# STMv1.net
KiCad netlist of a schematic drawn in EAGLE
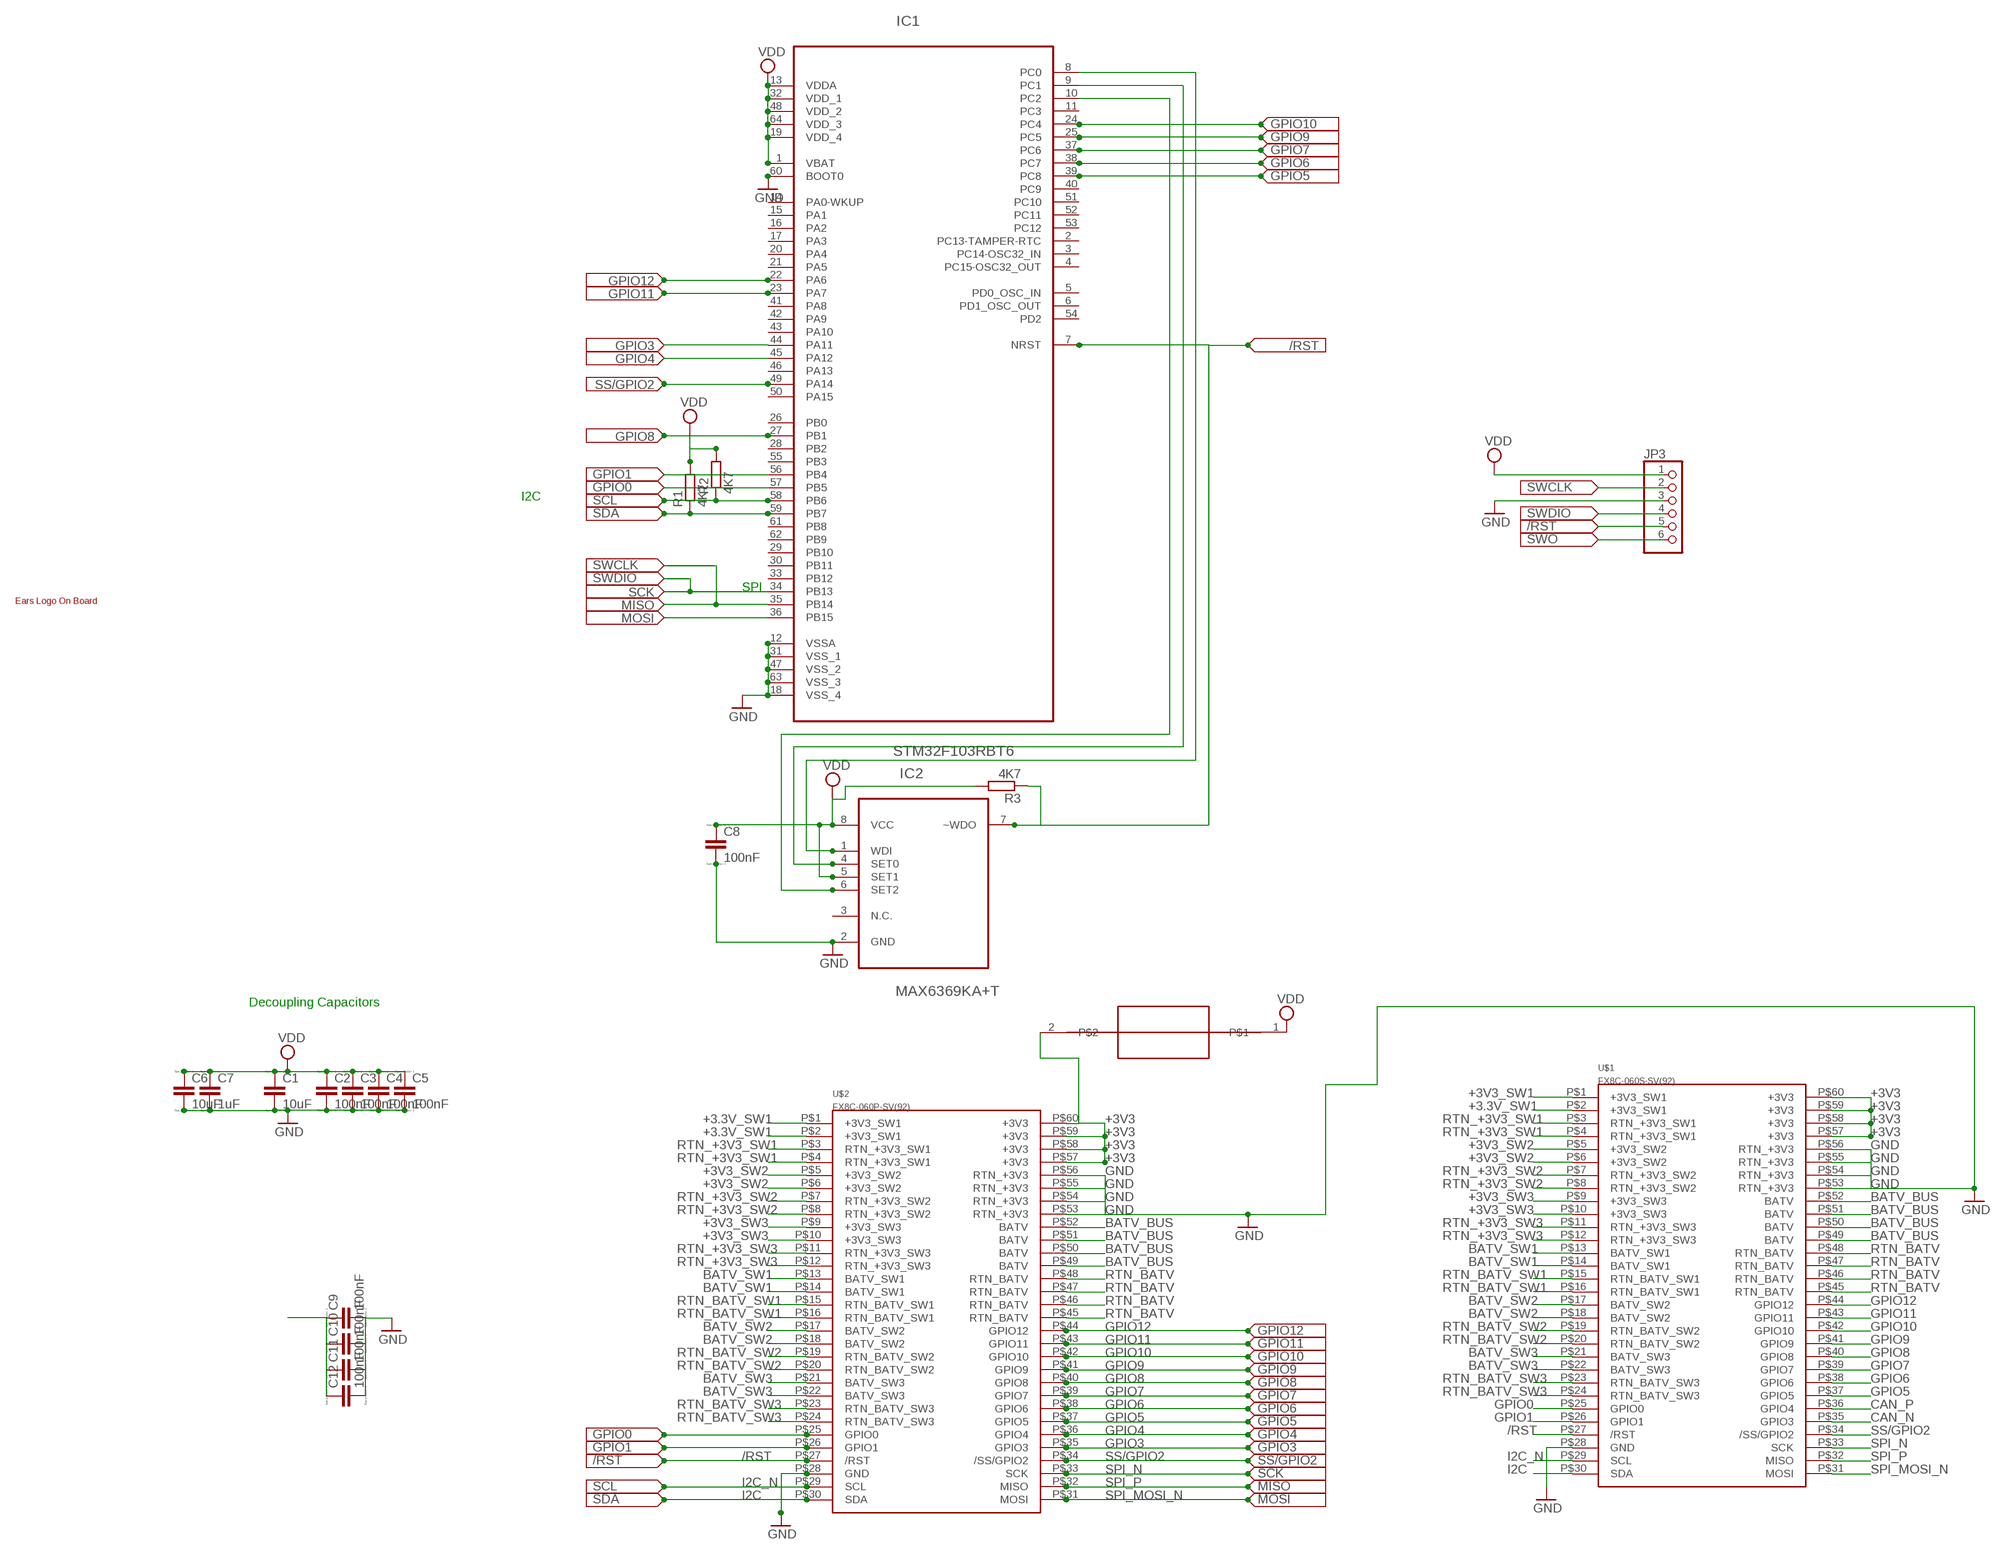
[diagram p0: schematic, sheet 1]

(export (version "E")
  (design (tool "Eeschema 10.0.6"))
  (components
    (comp (ref "C1")
      (value "10uF")
      (footprint "eagle-import:C0603")
      (libsource (lib "eagle-import") (part "CC0603"))
    )
    (comp (ref "C2")
      (value "100nF")
      (footprint "eagle-import:C0603")
      (libsource (lib "eagle-import") (part "CC0603"))
    )
    (comp (ref "C3")
      (value "100nF")
      (footprint "eagle-import:C0603")
      (libsource (lib "eagle-import") (part "CC0603"))
    )
    (comp (ref "C4")
      (value "100nF")
      (footprint "eagle-import:C0603")
      (libsource (lib "eagle-import") (part "CC0603"))
    )
    (comp (ref "C5")
      (value "100nF")
      (footprint "eagle-import:C0603")
      (libsource (lib "eagle-import") (part "CC0603"))
    )
    (comp (ref "C6")
      (value "10uF")
      (footprint "eagle-import:C0603")
      (libsource (lib "eagle-import") (part "CC0603"))
    )
    (comp (ref "C7")
      (value "1uF")
      (footprint "eagle-import:C0603")
      (libsource (lib "eagle-import") (part "CC0603"))
    )
    (comp (ref "C8")
      (value "100nF")
      (footprint "eagle-import:C0603")
      (libsource (lib "eagle-import") (part "CC0603"))
    )
    (comp (ref "C9")
      (value "100nF")
      (footprint "eagle-import:C0603")
      (libsource (lib "eagle-import") (part "CC0603"))
    )
    (comp (ref "C10")
      (value "100nF")
      (footprint "eagle-import:C0603")
      (libsource (lib "eagle-import") (part "CC0603"))
    )
    (comp (ref "C11")
      (value "100nF")
      (footprint "eagle-import:C0603")
      (libsource (lib "eagle-import") (part "CC0603"))
    )
    (comp (ref "C12")
      (value "100nF")
      (footprint "eagle-import:C0603")
      (libsource (lib "eagle-import") (part "CC0603"))
    )
    (comp (ref "FUSE")
      (value "0603POLYFUSE")
      (footprint "eagle-import:R0603")
      (libsource (lib "eagle-import") (part "0603POLYFUSE"))
    )
    (comp (ref "IC1")
      (value "STM32F103RBT6")
      (footprint "eagle-import:QFP50P1200X1200X160-64N")
      (libsource (lib "eagle-import") (part "STM32F103RBT6"))
    )
    (comp (ref "IC2")
      (value "MAX6369KA+T")
      (footprint "eagle-import:SOT65P280X145-8N")
      (libsource (lib "eagle-import") (part "MAX6369KA+T"))
    )
    (comp (ref "JP3")
      (value "PINHD-1X6")
      (footprint "eagle-import:1X06")
      (libsource (lib "eagle-import") (part "PINHD-1X6"))
    )
    (comp (ref "R1")
      (value "4K7")
      (footprint "eagle-import:R0603")
      (libsource (lib "eagle-import") (part "R-EU_R0603"))
    )
    (comp (ref "R2")
      (value "4K7")
      (footprint "eagle-import:R0603")
      (libsource (lib "eagle-import") (part "R-EU_R0603"))
    )
    (comp (ref "R3")
      (value "4K7")
      (footprint "eagle-import:R0603")
      (libsource (lib "eagle-import") (part "R-EU_R0603"))
    )
    (comp (ref "U$1")
      (value "FX8C-060S-SV(92)")
      (footprint "eagle-import:FX8C-060S-SV(92)")
      (libsource (lib "eagle-import") (part "FX8C-060S-SV(92)"))
    )
    (comp (ref "U$2")
      (value "FX8C-060P-SV(92)")
      (footprint "eagle-import:FX8C-060P-SV(92)")
      (libsource (lib "eagle-import") (part "FX8C-060P-SV(92)"))
    )
    (comp (ref "U$3")
      (value "EARSLOGOFULL")
      (footprint "eagle-import:EARSLOGOFULL")
      (libsource (lib "eagle-import") (part "EARSLOGOFULL"))
    )
  )
  (nets
    (net (code "1") (name "/+3.3V_SW1") (class "Default")
      (node (ref "U$1") (pin "P$2") (pinfunction "+3V3_SW1_P$2") (pintype "power_in"))
      (node (ref "U$2") (pin "P$1") (pinfunction "+3V3_SW1_P$1") (pintype "power_in"))
      (node (ref "U$2") (pin "P$2") (pinfunction "+3V3_SW1_P$2") (pintype "power_in"))
    )
    (net (code "2") (name "/+3V3") (class "Default")
      (node (ref "FUSE") (pin "2") (pinfunction "P$2_2") (pintype "bidirectional"))
      (node (ref "U$1") (pin "P$57") (pinfunction "+3V3_P$57") (pintype "power_in"))
      (node (ref "U$1") (pin "P$58") (pinfunction "+3V3_P$58") (pintype "power_in"))
      (node (ref "U$1") (pin "P$59") (pinfunction "+3V3_P$59") (pintype "power_in"))
      (node (ref "U$1") (pin "P$60") (pinfunction "+3V3_P$60") (pintype "power_in"))
      (node (ref "U$2") (pin "P$57") (pinfunction "+3V3_P$57") (pintype "power_in"))
      (node (ref "U$2") (pin "P$58") (pinfunction "+3V3_P$58") (pintype "power_in"))
      (node (ref "U$2") (pin "P$59") (pinfunction "+3V3_P$59") (pintype "power_in"))
      (node (ref "U$2") (pin "P$60") (pinfunction "+3V3_P$60") (pintype "power_in"))
    )
    (net (code "3") (name "/+3V3_SW1") (class "Default")
      (node (ref "U$1") (pin "P$1") (pinfunction "+3V3_SW1_P$1") (pintype "power_in"))
    )
    (net (code "4") (name "/+3V3_SW2") (class "Default")
      (node (ref "U$1") (pin "P$5") (pinfunction "+3V3_SW2_P$5") (pintype "power_in"))
      (node (ref "U$1") (pin "P$6") (pinfunction "+3V3_SW2_P$6") (pintype "power_in"))
      (node (ref "U$2") (pin "P$5") (pinfunction "+3V3_SW2_P$5") (pintype "power_in"))
      (node (ref "U$2") (pin "P$6") (pinfunction "+3V3_SW2_P$6") (pintype "power_in"))
    )
    (net (code "5") (name "/+3V3_SW3") (class "Default")
      (node (ref "U$1") (pin "P$10") (pinfunction "+3V3_SW3_P$10") (pintype "power_in"))
      (node (ref "U$1") (pin "P$9") (pinfunction "+3V3_SW3_P$9") (pintype "power_in"))
      (node (ref "U$2") (pin "P$10") (pinfunction "+3V3_SW3_P$10") (pintype "power_in"))
      (node (ref "U$2") (pin "P$9") (pinfunction "+3V3_SW3_P$9") (pintype "power_in"))
    )
    (net (code "6") (name "/BATV_BUS") (class "Default")
      (node (ref "U$1") (pin "P$49") (pinfunction "BATV_P$49") (pintype "power_in"))
      (node (ref "U$1") (pin "P$50") (pinfunction "BATV_P$50") (pintype "power_in"))
      (node (ref "U$1") (pin "P$51") (pinfunction "BATV_P$51") (pintype "power_in"))
      (node (ref "U$1") (pin "P$52") (pinfunction "BATV_P$52") (pintype "power_in"))
      (node (ref "U$2") (pin "P$49") (pinfunction "BATV_P$49") (pintype "power_in"))
      (node (ref "U$2") (pin "P$50") (pinfunction "BATV_P$50") (pintype "power_in"))
      (node (ref "U$2") (pin "P$51") (pinfunction "BATV_P$51") (pintype "power_in"))
      (node (ref "U$2") (pin "P$52") (pinfunction "BATV_P$52") (pintype "power_in"))
    )
    (net (code "7") (name "/BATV_SW1") (class "Default")
      (node (ref "U$1") (pin "P$13") (pinfunction "BATV_SW1_P$13") (pintype "power_in"))
      (node (ref "U$1") (pin "P$14") (pinfunction "BATV_SW1_P$14") (pintype "power_in"))
      (node (ref "U$2") (pin "P$13") (pinfunction "BATV_SW1_P$13") (pintype "power_in"))
      (node (ref "U$2") (pin "P$14") (pinfunction "BATV_SW1_P$14") (pintype "power_in"))
    )
    (net (code "8") (name "/BATV_SW2") (class "Default")
      (node (ref "U$1") (pin "P$17") (pinfunction "BATV_SW2_P$17") (pintype "power_in"))
      (node (ref "U$1") (pin "P$18") (pinfunction "BATV_SW2_P$18") (pintype "power_in"))
      (node (ref "U$2") (pin "P$17") (pinfunction "BATV_SW2_P$17") (pintype "power_in"))
      (node (ref "U$2") (pin "P$18") (pinfunction "BATV_SW2_P$18") (pintype "power_in"))
    )
    (net (code "9") (name "/BATV_SW3") (class "Default")
      (node (ref "U$1") (pin "P$21") (pinfunction "BATV_SW3_P$21") (pintype "power_in"))
      (node (ref "U$1") (pin "P$22") (pinfunction "BATV_SW3_P$22") (pintype "power_in"))
      (node (ref "U$2") (pin "P$21") (pinfunction "BATV_SW3_P$21") (pintype "power_in"))
      (node (ref "U$2") (pin "P$22") (pinfunction "BATV_SW3_P$22") (pintype "power_in"))
    )
    (net (code "10") (name "/CAN_N") (class "Default")
      (node (ref "U$1") (pin "P$35") (pinfunction "GPIO3_P$35") (pintype "bidirectional"))
    )
    (net (code "11") (name "/CAN_P") (class "Default")
      (node (ref "U$1") (pin "P$36") (pinfunction "GPIO4_P$36") (pintype "bidirectional"))
    )
    (net (code "12") (name "/GPIO0") (class "Default")
      (node (ref "IC1") (pin "57") (pinfunction "PB5_57") (pintype "bidirectional"))
      (node (ref "U$1") (pin "P$25") (pinfunction "GPIO0_P$25") (pintype "bidirectional"))
      (node (ref "U$2") (pin "P$25") (pinfunction "GPIO0_P$25") (pintype "bidirectional"))
    )
    (net (code "13") (name "/GPIO1") (class "Default")
      (node (ref "IC1") (pin "56") (pinfunction "PB4_56") (pintype "bidirectional"))
      (node (ref "U$1") (pin "P$26") (pinfunction "GPIO1_P$26") (pintype "bidirectional"))
      (node (ref "U$2") (pin "P$26") (pinfunction "GPIO1_P$26") (pintype "bidirectional"))
    )
    (net (code "14") (name "/GPIO3") (class "Default")
      (node (ref "IC1") (pin "44") (pinfunction "PA11_44") (pintype "bidirectional"))
      (node (ref "U$2") (pin "P$35") (pinfunction "GPIO3_P$35") (pintype "bidirectional"))
    )
    (net (code "15") (name "/GPIO4") (class "Default")
      (node (ref "IC1") (pin "45") (pinfunction "PA12_45") (pintype "bidirectional"))
      (node (ref "U$2") (pin "P$36") (pinfunction "GPIO4_P$36") (pintype "bidirectional"))
    )
    (net (code "16") (name "/GPIO5") (class "Default")
      (node (ref "IC1") (pin "39") (pinfunction "PC8_39") (pintype "bidirectional"))
      (node (ref "U$1") (pin "P$37") (pinfunction "GPIO5_P$37") (pintype "bidirectional"))
      (node (ref "U$2") (pin "P$37") (pinfunction "GPIO5_P$37") (pintype "bidirectional"))
    )
    (net (code "17") (name "/GPIO6") (class "Default")
      (node (ref "IC1") (pin "38") (pinfunction "PC7_38") (pintype "bidirectional"))
      (node (ref "U$1") (pin "P$38") (pinfunction "GPIO6_P$38") (pintype "bidirectional"))
      (node (ref "U$2") (pin "P$38") (pinfunction "GPIO6_P$38") (pintype "bidirectional"))
    )
    (net (code "18") (name "/GPIO7") (class "Default")
      (node (ref "IC1") (pin "37") (pinfunction "PC6_37") (pintype "bidirectional"))
      (node (ref "U$1") (pin "P$39") (pinfunction "GPIO7_P$39") (pintype "bidirectional"))
      (node (ref "U$2") (pin "P$39") (pinfunction "GPIO7_P$39") (pintype "bidirectional"))
    )
    (net (code "19") (name "/GPIO8") (class "Default")
      (node (ref "IC1") (pin "27") (pinfunction "PB1_27") (pintype "bidirectional"))
      (node (ref "U$1") (pin "P$40") (pinfunction "GPIO8_P$40") (pintype "bidirectional"))
      (node (ref "U$2") (pin "P$40") (pinfunction "GPIO8_P$40") (pintype "bidirectional"))
    )
    (net (code "20") (name "/GPIO9") (class "Default")
      (node (ref "IC1") (pin "25") (pinfunction "PC5_25") (pintype "bidirectional"))
      (node (ref "U$1") (pin "P$41") (pinfunction "GPIO9_P$41") (pintype "bidirectional"))
      (node (ref "U$2") (pin "P$41") (pinfunction "GPIO9_P$41") (pintype "bidirectional"))
    )
    (net (code "21") (name "/GPIO10") (class "Default")
      (node (ref "IC1") (pin "24") (pinfunction "PC4_24") (pintype "bidirectional"))
      (node (ref "U$1") (pin "P$42") (pinfunction "GPIO10_P$42") (pintype "bidirectional"))
      (node (ref "U$2") (pin "P$42") (pinfunction "GPIO10_P$42") (pintype "bidirectional"))
    )
    (net (code "22") (name "/GPIO11") (class "Default")
      (node (ref "IC1") (pin "23") (pinfunction "PA7_23") (pintype "bidirectional"))
      (node (ref "U$1") (pin "P$43") (pinfunction "GPIO11_P$43") (pintype "bidirectional"))
      (node (ref "U$2") (pin "P$43") (pinfunction "GPIO11_P$43") (pintype "bidirectional"))
    )
    (net (code "23") (name "/GPIO12") (class "Default")
      (node (ref "IC1") (pin "22") (pinfunction "PA6_22") (pintype "bidirectional"))
      (node (ref "U$1") (pin "P$44") (pinfunction "GPIO12_P$44") (pintype "bidirectional"))
      (node (ref "U$2") (pin "P$44") (pinfunction "GPIO12_P$44") (pintype "bidirectional"))
    )
    (net (code "24") (name "/I2C") (class "Default")
      (node (ref "IC1") (pin "59") (pinfunction "PB7_59") (pintype "bidirectional"))
      (node (ref "R1") (pin "1") (pinfunction "1_1") (pintype "passive"))
      (node (ref "U$1") (pin "P$30") (pinfunction "SDA_P$30") (pintype "bidirectional"))
      (node (ref "U$2") (pin "P$30") (pinfunction "SDA_P$30") (pintype "bidirectional"))
    )
    (net (code "25") (name "/I2C_N") (class "Default")
      (node (ref "IC1") (pin "58") (pinfunction "PB6_58") (pintype "bidirectional"))
      (node (ref "R2") (pin "1") (pinfunction "1_1") (pintype "passive"))
      (node (ref "U$1") (pin "P$29") (pinfunction "SCL_P$29") (pintype "bidirectional"))
      (node (ref "U$2") (pin "P$29") (pinfunction "SCL_P$29") (pintype "bidirectional"))
    )
    (net (code "26") (name "/RTN_+3V3_SW1") (class "Default")
      (node (ref "U$1") (pin "P$3") (pinfunction "RTN_+3V3_SW1_P$3") (pintype "power_in"))
      (node (ref "U$1") (pin "P$4") (pinfunction "RTN_+3V3_SW1_P$4") (pintype "power_in"))
      (node (ref "U$2") (pin "P$3") (pinfunction "RTN_+3V3_SW1_P$3") (pintype "power_in"))
      (node (ref "U$2") (pin "P$4") (pinfunction "RTN_+3V3_SW1_P$4") (pintype "power_in"))
    )
    (net (code "27") (name "/RTN_+3V3_SW2") (class "Default")
      (node (ref "U$1") (pin "P$7") (pinfunction "RTN_+3V3_SW2_P$7") (pintype "power_in"))
      (node (ref "U$1") (pin "P$8") (pinfunction "RTN_+3V3_SW2_P$8") (pintype "power_in"))
      (node (ref "U$2") (pin "P$7") (pinfunction "RTN_+3V3_SW2_P$7") (pintype "power_in"))
      (node (ref "U$2") (pin "P$8") (pinfunction "RTN_+3V3_SW2_P$8") (pintype "power_in"))
    )
    (net (code "28") (name "/RTN_+3V3_SW3") (class "Default")
      (node (ref "U$1") (pin "P$11") (pinfunction "RTN_+3V3_SW3_P$11") (pintype "power_in"))
      (node (ref "U$1") (pin "P$12") (pinfunction "RTN_+3V3_SW3_P$12") (pintype "power_in"))
      (node (ref "U$2") (pin "P$11") (pinfunction "RTN_+3V3_SW3_P$11") (pintype "power_in"))
      (node (ref "U$2") (pin "P$12") (pinfunction "RTN_+3V3_SW3_P$12") (pintype "power_in"))
    )
    (net (code "29") (name "/RTN_BATV") (class "Default")
      (node (ref "U$1") (pin "P$45") (pinfunction "RTN_BATV_P$45") (pintype "power_in"))
      (node (ref "U$1") (pin "P$46") (pinfunction "RTN_BATV_P$46") (pintype "power_in"))
      (node (ref "U$1") (pin "P$47") (pinfunction "RTN_BATV_P$47") (pintype "power_in"))
      (node (ref "U$1") (pin "P$48") (pinfunction "RTN_BATV_P$48") (pintype "power_in"))
      (node (ref "U$2") (pin "P$45") (pinfunction "RTN_BATV_P$45") (pintype "power_in"))
      (node (ref "U$2") (pin "P$46") (pinfunction "RTN_BATV_P$46") (pintype "power_in"))
      (node (ref "U$2") (pin "P$47") (pinfunction "RTN_BATV_P$47") (pintype "power_in"))
      (node (ref "U$2") (pin "P$48") (pinfunction "RTN_BATV_P$48") (pintype "power_in"))
    )
    (net (code "30") (name "/RTN_BATV_SW1") (class "Default")
      (node (ref "U$1") (pin "P$15") (pinfunction "RTN_BATV_SW1_P$15") (pintype "power_in"))
      (node (ref "U$1") (pin "P$16") (pinfunction "RTN_BATV_SW1_P$16") (pintype "power_in"))
      (node (ref "U$2") (pin "P$15") (pinfunction "RTN_BATV_SW1_P$15") (pintype "power_in"))
      (node (ref "U$2") (pin "P$16") (pinfunction "RTN_BATV_SW1_P$16") (pintype "power_in"))
    )
    (net (code "31") (name "/RTN_BATV_SW2") (class "Default")
      (node (ref "U$1") (pin "P$19") (pinfunction "RTN_BATV_SW2_P$19") (pintype "power_in"))
      (node (ref "U$1") (pin "P$20") (pinfunction "RTN_BATV_SW2_P$20") (pintype "power_in"))
      (node (ref "U$2") (pin "P$19") (pinfunction "RTN_BATV_SW2_P$19") (pintype "power_in"))
      (node (ref "U$2") (pin "P$20") (pinfunction "RTN_BATV_SW2_P$20") (pintype "power_in"))
    )
    (net (code "32") (name "/RTN_BATV_SW3") (class "Default")
      (node (ref "U$1") (pin "P$23") (pinfunction "RTN_BATV_SW3_P$23") (pintype "power_in"))
      (node (ref "U$1") (pin "P$24") (pinfunction "RTN_BATV_SW3_P$24") (pintype "power_in"))
      (node (ref "U$2") (pin "P$23") (pinfunction "RTN_BATV_SW3_P$23") (pintype "power_in"))
      (node (ref "U$2") (pin "P$24") (pinfunction "RTN_BATV_SW3_P$24") (pintype "power_in"))
    )
    (net (code "33") (name "/SPI_MOSI_N") (class "Default")
      (node (ref "IC1") (pin "36") (pinfunction "PB15_36") (pintype "bidirectional"))
      (node (ref "U$1") (pin "P$31") (pinfunction "MOSI_P$31") (pintype "bidirectional"))
      (node (ref "U$2") (pin "P$31") (pinfunction "MOSI_P$31") (pintype "bidirectional"))
    )
    (net (code "34") (name "/SPI_N") (class "Default")
      (node (ref "IC1") (pin "34") (pinfunction "PB13_34") (pintype "bidirectional"))
      (node (ref "JP3") (pin "4") (pinfunction "SWDIO_4") (pintype "passive"))
      (node (ref "U$1") (pin "P$33") (pinfunction "SCK_P$33") (pintype "bidirectional"))
      (node (ref "U$2") (pin "P$33") (pinfunction "SCK_P$33") (pintype "bidirectional"))
    )
    (net (code "35") (name "/SPI_P") (class "Default")
      (node (ref "IC1") (pin "35") (pinfunction "PB14_35") (pintype "bidirectional"))
      (node (ref "JP3") (pin "2") (pinfunction "SWCLK_2") (pintype "passive"))
      (node (ref "U$1") (pin "P$32") (pinfunction "MISO_P$32") (pintype "bidirectional"))
      (node (ref "U$2") (pin "P$32") (pinfunction "MISO_P$32") (pintype "bidirectional"))
    )
    (net (code "36") (name "/SS{slash}GPIO2") (class "Default")
      (node (ref "IC1") (pin "49") (pinfunction "PA14_49") (pintype "bidirectional"))
      (node (ref "U$1") (pin "P$34") (pinfunction "/SS/GPIO2_P$34") (pintype "bidirectional"))
      (node (ref "U$2") (pin "P$34") (pinfunction "/SS/GPIO2_P$34") (pintype "bidirectional"))
    )
    (net (code "37") (name "/{slash}RST") (class "Default")
      (node (ref "IC1") (pin "7") (pinfunction "NRST_7") (pintype "bidirectional"))
      (node (ref "IC2") (pin "7") (pinfunction "~{WDO}_7") (pintype "output"))
      (node (ref "R3") (pin "1") (pinfunction "1_1") (pintype "passive"))
      (node (ref "U$1") (pin "P$27") (pinfunction "/RST_P$27") (pintype "bidirectional"))
      (node (ref "U$2") (pin "P$27") (pinfunction "/RST_P$27") (pintype "bidirectional"))
    )
    (net (code "38") (name "GND") (class "Default")
      (node (ref "C1") (pin "2") (pinfunction "2_2") (pintype "passive"))
      (node (ref "C10") (pin "2") (pinfunction "2_2") (pintype "passive"))
      (node (ref "C11") (pin "2") (pinfunction "2_2") (pintype "passive"))
      (node (ref "C12") (pin "2") (pinfunction "2_2") (pintype "passive"))
      (node (ref "C2") (pin "2") (pinfunction "2_2") (pintype "passive"))
      (node (ref "C3") (pin "2") (pinfunction "2_2") (pintype "passive"))
      (node (ref "C4") (pin "2") (pinfunction "2_2") (pintype "passive"))
      (node (ref "C5") (pin "2") (pinfunction "2_2") (pintype "passive"))
      (node (ref "C6") (pin "2") (pinfunction "2_2") (pintype "passive"))
      (node (ref "C7") (pin "2") (pinfunction "2_2") (pintype "passive"))
      (node (ref "C8") (pin "2") (pinfunction "2_2") (pintype "passive"))
      (node (ref "C9") (pin "2") (pinfunction "2_2") (pintype "passive"))
      (node (ref "IC1") (pin "12") (pinfunction "VSSA_12") (pintype "passive"))
      (node (ref "IC1") (pin "18") (pinfunction "VSS_4_18") (pintype "passive"))
      (node (ref "IC1") (pin "31") (pinfunction "VSS_1_31") (pintype "passive"))
      (node (ref "IC1") (pin "47") (pinfunction "VSS_2_47") (pintype "passive"))
      (node (ref "IC1") (pin "60") (pinfunction "BOOT0_60") (pintype "input"))
      (node (ref "IC1") (pin "63") (pinfunction "VSS_3_63") (pintype "passive"))
      (node (ref "IC2") (pin "2") (pinfunction "GND_2") (pintype "passive"))
      (node (ref "JP3") (pin "3") (pinfunction "GND_3") (pintype "passive"))
      (node (ref "U$1") (pin "P$28") (pinfunction "GND_P$28") (pintype "bidirectional"))
      (node (ref "U$1") (pin "P$53") (pinfunction "RTN_+3V3_P$53") (pintype "power_in"))
      (node (ref "U$1") (pin "P$54") (pinfunction "RTN_+3V3_P$54") (pintype "power_in"))
      (node (ref "U$1") (pin "P$55") (pinfunction "RTN_+3V3_P$55") (pintype "power_in"))
      (node (ref "U$1") (pin "P$56") (pinfunction "RTN_+3V3_P$56") (pintype "power_in"))
      (node (ref "U$2") (pin "P$28") (pinfunction "GND_P$28") (pintype "bidirectional"))
      (node (ref "U$2") (pin "P$53") (pinfunction "RTN_+3V3_P$53") (pintype "power_in"))
      (node (ref "U$2") (pin "P$54") (pinfunction "RTN_+3V3_P$54") (pintype "power_in"))
      (node (ref "U$2") (pin "P$55") (pinfunction "RTN_+3V3_P$55") (pintype "power_in"))
      (node (ref "U$2") (pin "P$56") (pinfunction "RTN_+3V3_P$56") (pintype "power_in"))
    )
    (net (code "39") (name "Net-(C10-Pad1)") (class "Default")
      (node (ref "C10") (pin "1") (pinfunction "1_1") (pintype "passive"))
      (node (ref "C11") (pin "1") (pinfunction "1_1") (pintype "passive"))
      (node (ref "C12") (pin "1") (pinfunction "1_1") (pintype "passive"))
      (node (ref "C9") (pin "1") (pinfunction "1_1") (pintype "passive"))
    )
    (net (code "40") (name "Net-(IC1-PC0)") (class "Default")
      (node (ref "IC1") (pin "8") (pinfunction "PC0_8") (pintype "bidirectional"))
      (node (ref "IC2") (pin "1") (pinfunction "WDI_1") (pintype "input"))
    )
    (net (code "41") (name "Net-(IC1-PC1)") (class "Default")
      (node (ref "IC1") (pin "9") (pinfunction "PC1_9") (pintype "bidirectional"))
      (node (ref "IC2") (pin "4") (pinfunction "SET0_4") (pintype "input"))
    )
    (net (code "42") (name "Net-(IC1-PC2)") (class "Default")
      (node (ref "IC1") (pin "10") (pinfunction "PC2_10") (pintype "bidirectional"))
      (node (ref "IC2") (pin "6") (pinfunction "SET2_6") (pintype "input"))
    )
    (net (code "43") (name "VDD") (class "Default")
      (node (ref "C1") (pin "1") (pinfunction "1_1") (pintype "passive"))
      (node (ref "C2") (pin "1") (pinfunction "1_1") (pintype "passive"))
      (node (ref "C3") (pin "1") (pinfunction "1_1") (pintype "passive"))
      (node (ref "C4") (pin "1") (pinfunction "1_1") (pintype "passive"))
      (node (ref "C5") (pin "1") (pinfunction "1_1") (pintype "passive"))
      (node (ref "C6") (pin "1") (pinfunction "1_1") (pintype "passive"))
      (node (ref "C7") (pin "1") (pinfunction "1_1") (pintype "passive"))
      (node (ref "C8") (pin "1") (pinfunction "1_1") (pintype "passive"))
      (node (ref "FUSE") (pin "1") (pinfunction "P$1_1") (pintype "bidirectional"))
      (node (ref "IC1") (pin "1") (pinfunction "VBAT_1") (pintype "input"))
      (node (ref "IC1") (pin "13") (pinfunction "VDDA_13") (pintype "power_in"))
      (node (ref "IC1") (pin "19") (pinfunction "VDD_4_19") (pintype "power_in"))
      (node (ref "IC1") (pin "32") (pinfunction "VDD_1_32") (pintype "power_in"))
      (node (ref "IC1") (pin "48") (pinfunction "VDD_2_48") (pintype "power_in"))
      (node (ref "IC1") (pin "64") (pinfunction "VDD_3_64") (pintype "power_in"))
      (node (ref "IC2") (pin "5") (pinfunction "SET1_5") (pintype "input"))
      (node (ref "IC2") (pin "8") (pinfunction "VCC_8") (pintype "power_in"))
      (node (ref "JP3") (pin "1") (pinfunction "VDD_1") (pintype "passive"))
      (node (ref "R1") (pin "2") (pinfunction "2_2") (pintype "passive"))
      (node (ref "R2") (pin "2") (pinfunction "2_2") (pintype "passive"))
      (node (ref "R3") (pin "2") (pinfunction "2_2") (pintype "passive"))
    )
    (net (code "44") (name "unconnected-(IC1-PA0-WKUP-Pad14)") (class "Default")
      (node (ref "IC1") (pin "14") (pinfunction "PA0-WKUP_14") (pintype "bidirectional"))
    )
    (net (code "45") (name "unconnected-(IC1-PA1-Pad15)") (class "Default")
      (node (ref "IC1") (pin "15") (pinfunction "PA1_15") (pintype "bidirectional"))
    )
    (net (code "46") (name "unconnected-(IC1-PA2-Pad16)") (class "Default")
      (node (ref "IC1") (pin "16") (pinfunction "PA2_16") (pintype "bidirectional"))
    )
    (net (code "47") (name "unconnected-(IC1-PA3-Pad17)") (class "Default")
      (node (ref "IC1") (pin "17") (pinfunction "PA3_17") (pintype "bidirectional"))
    )
    (net (code "48") (name "unconnected-(IC1-PA4-Pad20)") (class "Default")
      (node (ref "IC1") (pin "20") (pinfunction "PA4_20") (pintype "bidirectional"))
    )
    (net (code "49") (name "unconnected-(IC1-PA5-Pad21)") (class "Default")
      (node (ref "IC1") (pin "21") (pinfunction "PA5_21") (pintype "bidirectional"))
    )
    (net (code "50") (name "unconnected-(IC1-PA8-Pad41)") (class "Default")
      (node (ref "IC1") (pin "41") (pinfunction "PA8_41") (pintype "bidirectional"))
    )
    (net (code "51") (name "unconnected-(IC1-PA9-Pad42)") (class "Default")
      (node (ref "IC1") (pin "42") (pinfunction "PA9_42") (pintype "bidirectional"))
    )
    (net (code "52") (name "unconnected-(IC1-PA10-Pad43)") (class "Default")
      (node (ref "IC1") (pin "43") (pinfunction "PA10_43") (pintype "bidirectional"))
    )
    (net (code "53") (name "unconnected-(IC1-PA13-Pad46)") (class "Default")
      (node (ref "IC1") (pin "46") (pinfunction "PA13_46") (pintype "bidirectional"))
    )
    (net (code "54") (name "unconnected-(IC1-PA15-Pad50)") (class "Default")
      (node (ref "IC1") (pin "50") (pinfunction "PA15_50") (pintype "bidirectional"))
    )
    (net (code "55") (name "unconnected-(IC1-PB0-Pad26)") (class "Default")
      (node (ref "IC1") (pin "26") (pinfunction "PB0_26") (pintype "bidirectional"))
    )
    (net (code "56") (name "unconnected-(IC1-PB2-Pad28)") (class "Default")
      (node (ref "IC1") (pin "28") (pinfunction "PB2_28") (pintype "bidirectional"))
    )
    (net (code "57") (name "unconnected-(IC1-PB3-Pad55)") (class "Default")
      (node (ref "IC1") (pin "55") (pinfunction "PB3_55") (pintype "bidirectional"))
    )
    (net (code "58") (name "unconnected-(IC1-PB8-Pad61)") (class "Default")
      (node (ref "IC1") (pin "61") (pinfunction "PB8_61") (pintype "bidirectional"))
    )
    (net (code "59") (name "unconnected-(IC1-PB9-Pad62)") (class "Default")
      (node (ref "IC1") (pin "62") (pinfunction "PB9_62") (pintype "bidirectional"))
    )
    (net (code "60") (name "unconnected-(IC1-PB10-Pad29)") (class "Default")
      (node (ref "IC1") (pin "29") (pinfunction "PB10_29") (pintype "bidirectional"))
    )
    (net (code "61") (name "unconnected-(IC1-PB11-Pad30)") (class "Default")
      (node (ref "IC1") (pin "30") (pinfunction "PB11_30") (pintype "bidirectional"))
    )
    (net (code "62") (name "unconnected-(IC1-PB12-Pad33)") (class "Default")
      (node (ref "IC1") (pin "33") (pinfunction "PB12_33") (pintype "bidirectional"))
    )
    (net (code "63") (name "unconnected-(IC1-PC3-Pad11)") (class "Default")
      (node (ref "IC1") (pin "11") (pinfunction "PC3_11") (pintype "bidirectional"))
    )
    (net (code "64") (name "unconnected-(IC1-PC9-Pad40)") (class "Default")
      (node (ref "IC1") (pin "40") (pinfunction "PC9_40") (pintype "bidirectional"))
    )
    (net (code "65") (name "unconnected-(IC1-PC10-Pad51)") (class "Default")
      (node (ref "IC1") (pin "51") (pinfunction "PC10_51") (pintype "bidirectional"))
    )
    (net (code "66") (name "unconnected-(IC1-PC11-Pad52)") (class "Default")
      (node (ref "IC1") (pin "52") (pinfunction "PC11_52") (pintype "bidirectional"))
    )
    (net (code "67") (name "unconnected-(IC1-PC12-Pad53)") (class "Default")
      (node (ref "IC1") (pin "53") (pinfunction "PC12_53") (pintype "bidirectional"))
    )
    (net (code "68") (name "unconnected-(IC1-PC13-TAMPER-RTC-Pad2)") (class "Default")
      (node (ref "IC1") (pin "2") (pinfunction "PC13-TAMPER-RTC_2") (pintype "bidirectional"))
    )
    (net (code "69") (name "unconnected-(IC1-PC14-OSC32_IN-Pad3)") (class "Default")
      (node (ref "IC1") (pin "3") (pinfunction "PC14-OSC32_IN_3") (pintype "bidirectional"))
    )
    (net (code "70") (name "unconnected-(IC1-PC15-OSC32_OUT-Pad4)") (class "Default")
      (node (ref "IC1") (pin "4") (pinfunction "PC15-OSC32_OUT_4") (pintype "bidirectional"))
    )
    (net (code "71") (name "unconnected-(IC1-PD0_OSC_IN-Pad5)") (class "Default")
      (node (ref "IC1") (pin "5") (pinfunction "PD0_OSC_IN_5") (pintype "bidirectional"))
    )
    (net (code "72") (name "unconnected-(IC1-PD1_OSC_OUT-Pad6)") (class "Default")
      (node (ref "IC1") (pin "6") (pinfunction "PD1_OSC_OUT_6") (pintype "bidirectional"))
    )
    (net (code "73") (name "unconnected-(IC1-PD2-Pad54)") (class "Default")
      (node (ref "IC1") (pin "54") (pinfunction "PD2_54") (pintype "bidirectional"))
    )
    (net (code "74") (name "unconnected-(IC2-N.C.-Pad3)") (class "Default")
      (node (ref "IC2") (pin "3") (pinfunction "N.C._3") (pintype "no_connect"))
    )
    (net (code "75") (name "unconnected-(JP3-NRST-Pad5)") (class "Default")
      (node (ref "JP3") (pin "5") (pinfunction "NRST_5") (pintype "passive"))
    )
    (net (code "76") (name "unconnected-(JP3-SWO-Pad6)") (class "Default")
      (node (ref "JP3") (pin "6") (pinfunction "SWO_6") (pintype "passive"))
    )
  )
)
